# Thermocouple_Module.net
KiCad netlist of a schematic drawn in EAGLE
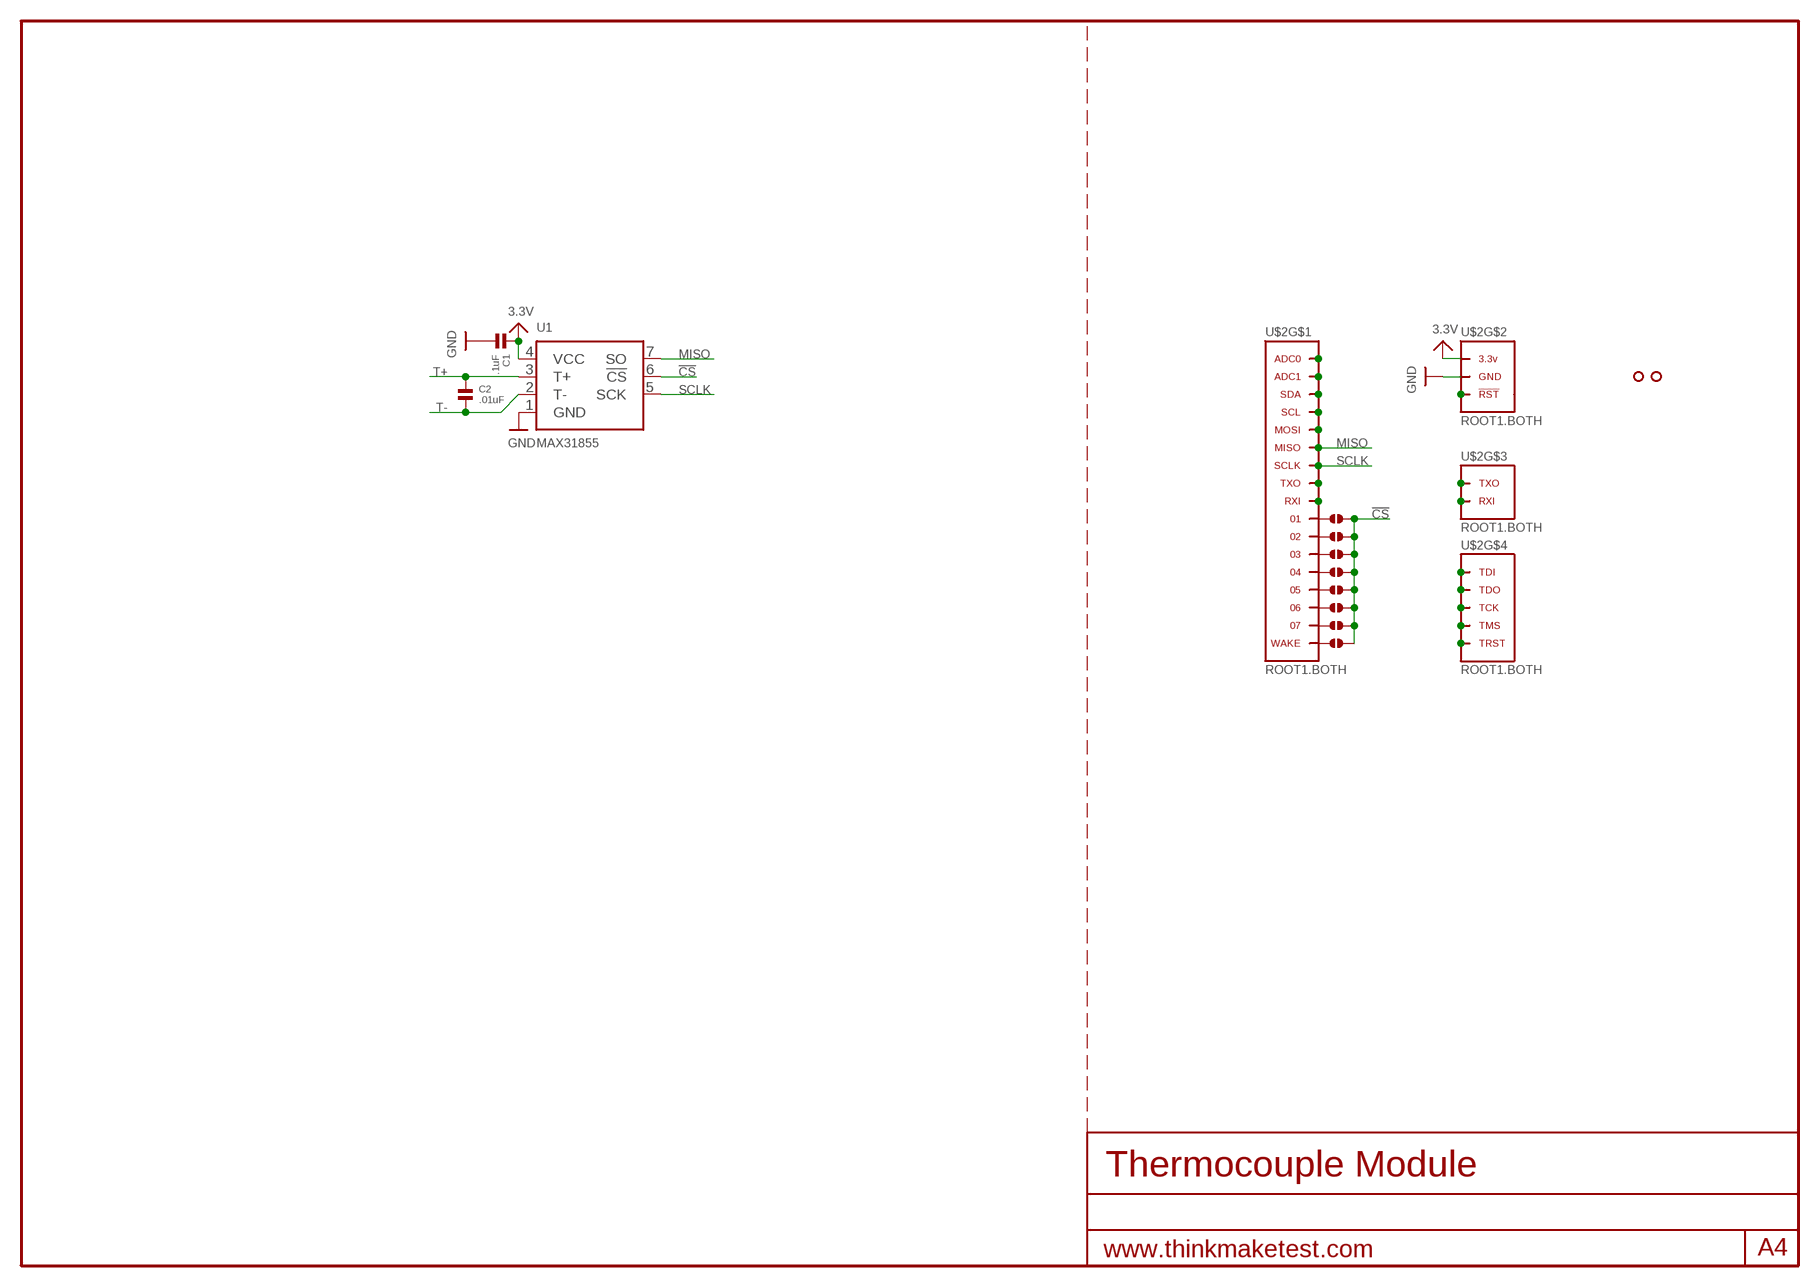
[diagram p0: schematic, sheet 1]

(export (version "E")
  (design (tool "Eeschema 10.0.6"))
  (components
    (comp (ref "C1")
      (value ".1uF")
      (footprint "eagle-import:0603")
      (libsource (lib "eagle-import") (part "CAPACITOR.0603"))
    )
    (comp (ref "C2")
      (value ".01uF")
      (footprint "eagle-import:0603")
      (libsource (lib "eagle-import") (part "CAPACITOR.0603"))
    )
    (comp (ref "J1")
      (value "SOLDERJUMPER.2.SML")
      (footprint "eagle-import:2.SML")
      (libsource (lib "eagle-import") (part "SOLDERJUMPER.2.SML"))
    )
    (comp (ref "J2")
      (value "SOLDERJUMPER.2.SML")
      (footprint "eagle-import:2.SML")
      (libsource (lib "eagle-import") (part "SOLDERJUMPER.2.SML"))
    )
    (comp (ref "J3")
      (value "SOLDERJUMPER.2.SML")
      (footprint "eagle-import:2.SML")
      (libsource (lib "eagle-import") (part "SOLDERJUMPER.2.SML"))
    )
    (comp (ref "J4")
      (value "SOLDERJUMPER.2.SML")
      (footprint "eagle-import:2.SML")
      (libsource (lib "eagle-import") (part "SOLDERJUMPER.2.SML"))
    )
    (comp (ref "J5")
      (value "SOLDERJUMPER.2.SML")
      (footprint "eagle-import:2.SML")
      (libsource (lib "eagle-import") (part "SOLDERJUMPER.2.SML"))
    )
    (comp (ref "J6")
      (value "SOLDERJUMPER.2.SML")
      (footprint "eagle-import:2.SML")
      (libsource (lib "eagle-import") (part "SOLDERJUMPER.2.SML"))
    )
    (comp (ref "J7")
      (value "SOLDERJUMPER.2.SML")
      (footprint "eagle-import:2.SML")
      (libsource (lib "eagle-import") (part "SOLDERJUMPER.2.SML"))
    )
    (comp (ref "J8")
      (value "SOLDERJUMPER.2.SML")
      (footprint "eagle-import:2.SML")
      (libsource (lib "eagle-import") (part "SOLDERJUMPER.2.SML"))
    )
    (comp (ref "U$2")
      (value "ROOT1.BOTH")
      (footprint "eagle-import:ROOT1.BOTH")
      (libsource (lib "eagle-import") (part "ROOT1.BOTH"))
    )
    (comp (ref "U$3")
      (value "HOLE.2MM")
      (footprint "eagle-import:2MM")
      (libsource (lib "eagle-import") (part "HOLE.2MM"))
    )
    (comp (ref "U$4")
      (value "HOLE.2MM")
      (footprint "eagle-import:2MM")
      (libsource (lib "eagle-import") (part "HOLE.2MM"))
    )
    (comp (ref "U1")
      (value "MAX31855")
      (footprint "eagle-import:SO08")
      (libsource (lib "eagle-import") (part "MAX31855"))
    )
  )
  (nets
    (net (code "1") (name "/MISO") (class "Default")
      (node (ref "U$2") (pin "MISO") (pinfunction "MISO_MISO") (pintype "bidirectional"))
      (node (ref "U$2") (pin "MISO@1") (pinfunction "MISO_MISO@1") (pintype "bidirectional"))
      (node (ref "U$2") (pin "MISO@VIA") (pinfunction "MISO_MISO@VIA") (pintype "bidirectional"))
      (node (ref "U1") (pin "7") (pinfunction "SO_7") (pintype "bidirectional"))
    )
    (net (code "2") (name "/SCLK") (class "Default")
      (node (ref "U$2") (pin "SCLK") (pinfunction "SCLK_SCLK") (pintype "bidirectional"))
      (node (ref "U$2") (pin "SCLK@1") (pinfunction "SCLK_SCLK@1") (pintype "bidirectional"))
      (node (ref "U$2") (pin "SCLK@VIA") (pinfunction "SCLK_SCLK@VIA") (pintype "bidirectional"))
      (node (ref "U1") (pin "5") (pinfunction "SCK_5") (pintype "bidirectional"))
    )
    (net (code "3") (name "/T+") (class "Default")
      (node (ref "C2") (pin "1") (pinfunction "1_1") (pintype "bidirectional"))
      (node (ref "U1") (pin "3") (pinfunction "T+_3") (pintype "bidirectional"))
    )
    (net (code "4") (name "/T-") (class "Default")
      (node (ref "C2") (pin "2") (pinfunction "2_2") (pintype "bidirectional"))
      (node (ref "U1") (pin "2") (pinfunction "T-_2") (pintype "bidirectional"))
    )
    (net (code "5") (name "/~{CS}") (class "Default")
      (node (ref "J1") (pin "2") (pinfunction "2_2") (pintype "bidirectional"))
      (node (ref "J2") (pin "2") (pinfunction "2_2") (pintype "bidirectional"))
      (node (ref "J3") (pin "2") (pinfunction "2_2") (pintype "bidirectional"))
      (node (ref "J4") (pin "2") (pinfunction "2_2") (pintype "bidirectional"))
      (node (ref "J5") (pin "2") (pinfunction "2_2") (pintype "bidirectional"))
      (node (ref "J6") (pin "2") (pinfunction "2_2") (pintype "bidirectional"))
      (node (ref "J7") (pin "2") (pinfunction "2_2") (pintype "bidirectional"))
      (node (ref "J8") (pin "2") (pinfunction "2_2") (pintype "bidirectional"))
      (node (ref "U1") (pin "6") (pinfunction "~{CS}_6") (pintype "bidirectional"))
    )
    (net (code "6") (name "3.3V") (class "Default")
      (node (ref "C1") (pin "1") (pinfunction "1_1") (pintype "bidirectional"))
      (node (ref "U$2") (pin "3.3V@1") (pinfunction "3.3V_3.3V@1") (pintype "bidirectional"))
      (node (ref "U$2") (pin "3.3V@10") (pinfunction "3.3V_3.3V@10") (pintype "bidirectional"))
      (node (ref "U$2") (pin "3.3V@11") (pinfunction "3.3V_3.3V@11") (pintype "bidirectional"))
      (node (ref "U$2") (pin "3.3V@12") (pinfunction "3.3V_3.3V@12") (pintype "bidirectional"))
      (node (ref "U$2") (pin "3.3V@13") (pinfunction "3.3V_3.3V@13") (pintype "bidirectional"))
      (node (ref "U$2") (pin "3.3V@14") (pinfunction "3.3V_3.3V@14") (pintype "bidirectional"))
      (node (ref "U$2") (pin "3.3V@15") (pinfunction "3.3V_3.3V@15") (pintype "bidirectional"))
      (node (ref "U$2") (pin "3.3V@16") (pinfunction "3.3V_3.3V@16") (pintype "bidirectional"))
      (node (ref "U$2") (pin "3.3V@17") (pinfunction "3.3V_3.3V@17") (pintype "bidirectional"))
      (node (ref "U$2") (pin "3.3V@18") (pinfunction "3.3V_3.3V@18") (pintype "bidirectional"))
      (node (ref "U$2") (pin "3.3V@19") (pinfunction "3.3V_3.3V@19") (pintype "bidirectional"))
      (node (ref "U$2") (pin "3.3V@2") (pinfunction "3.3V_3.3V@2") (pintype "bidirectional"))
      (node (ref "U$2") (pin "3.3V@20") (pinfunction "3.3V_3.3V@20") (pintype "bidirectional"))
      (node (ref "U$2") (pin "3.3V@21") (pinfunction "3.3V_3.3V@21") (pintype "bidirectional"))
      (node (ref "U$2") (pin "3.3V@22") (pinfunction "3.3V_3.3V@22") (pintype "bidirectional"))
      (node (ref "U$2") (pin "3.3V@23") (pinfunction "3.3V_3.3V@23") (pintype "bidirectional"))
      (node (ref "U$2") (pin "3.3V@24") (pinfunction "3.3V_3.3V@24") (pintype "bidirectional"))
      (node (ref "U$2") (pin "3.3V@3") (pinfunction "3.3V_3.3V@3") (pintype "bidirectional"))
      (node (ref "U$2") (pin "3.3V@4") (pinfunction "3.3V_3.3V@4") (pintype "bidirectional"))
      (node (ref "U$2") (pin "3.3V@5") (pinfunction "3.3V_3.3V@5") (pintype "bidirectional"))
      (node (ref "U$2") (pin "3.3V@6") (pinfunction "3.3V_3.3V@6") (pintype "bidirectional"))
      (node (ref "U$2") (pin "3.3V@7") (pinfunction "3.3V_3.3V@7") (pintype "bidirectional"))
      (node (ref "U$2") (pin "3.3V@8") (pinfunction "3.3V_3.3V@8") (pintype "bidirectional"))
      (node (ref "U$2") (pin "3.3V@9") (pinfunction "3.3V_3.3V@9") (pintype "bidirectional"))
      (node (ref "U$2") (pin "3.3V@VIA") (pinfunction "3.3V_3.3V@VIA") (pintype "bidirectional"))
      (node (ref "U1") (pin "4") (pinfunction "VCC_4") (pintype "bidirectional"))
    )
    (net (code "7") (name "GND") (class "Default")
      (node (ref "C1") (pin "2") (pinfunction "2_2") (pintype "bidirectional"))
      (node (ref "U$2") (pin "GND@1") (pinfunction "GND_GND@1") (pintype "bidirectional"))
      (node (ref "U$2") (pin "GND@10") (pinfunction "GND_GND@10") (pintype "bidirectional"))
      (node (ref "U$2") (pin "GND@11") (pinfunction "GND_GND@11") (pintype "bidirectional"))
      (node (ref "U$2") (pin "GND@12") (pinfunction "GND_GND@12") (pintype "bidirectional"))
      (node (ref "U$2") (pin "GND@13") (pinfunction "GND_GND@13") (pintype "bidirectional"))
      (node (ref "U$2") (pin "GND@14") (pinfunction "GND_GND@14") (pintype "bidirectional"))
      (node (ref "U$2") (pin "GND@15") (pinfunction "GND_GND@15") (pintype "bidirectional"))
      (node (ref "U$2") (pin "GND@16") (pinfunction "GND_GND@16") (pintype "bidirectional"))
      (node (ref "U$2") (pin "GND@17") (pinfunction "GND_GND@17") (pintype "bidirectional"))
      (node (ref "U$2") (pin "GND@18") (pinfunction "GND_GND@18") (pintype "bidirectional"))
      (node (ref "U$2") (pin "GND@19") (pinfunction "GND_GND@19") (pintype "bidirectional"))
      (node (ref "U$2") (pin "GND@2") (pinfunction "GND_GND@2") (pintype "bidirectional"))
      (node (ref "U$2") (pin "GND@20") (pinfunction "GND_GND@20") (pintype "bidirectional"))
      (node (ref "U$2") (pin "GND@21") (pinfunction "GND_GND@21") (pintype "bidirectional"))
      (node (ref "U$2") (pin "GND@22") (pinfunction "GND_GND@22") (pintype "bidirectional"))
      (node (ref "U$2") (pin "GND@23") (pinfunction "GND_GND@23") (pintype "bidirectional"))
      (node (ref "U$2") (pin "GND@24") (pinfunction "GND_GND@24") (pintype "bidirectional"))
      (node (ref "U$2") (pin "GND@25") (pinfunction "GND_GND@25") (pintype "bidirectional"))
      (node (ref "U$2") (pin "GND@26") (pinfunction "GND_GND@26") (pintype "bidirectional"))
      (node (ref "U$2") (pin "GND@3") (pinfunction "GND_GND@3") (pintype "bidirectional"))
      (node (ref "U$2") (pin "GND@4") (pinfunction "GND_GND@4") (pintype "bidirectional"))
      (node (ref "U$2") (pin "GND@5") (pinfunction "GND_GND@5") (pintype "bidirectional"))
      (node (ref "U$2") (pin "GND@6") (pinfunction "GND_GND@6") (pintype "bidirectional"))
      (node (ref "U$2") (pin "GND@7") (pinfunction "GND_GND@7") (pintype "bidirectional"))
      (node (ref "U$2") (pin "GND@8") (pinfunction "GND_GND@8") (pintype "bidirectional"))
      (node (ref "U$2") (pin "GND@9") (pinfunction "GND_GND@9") (pintype "bidirectional"))
      (node (ref "U$2") (pin "GND@VIA") (pinfunction "GND_GND@VIA") (pintype "bidirectional"))
      (node (ref "U1") (pin "1") (pinfunction "GND_1") (pintype "bidirectional"))
    )
    (net (code "8") (name "Net-(J1-Pad1)") (class "Default")
      (node (ref "J1") (pin "1") (pinfunction "1_1") (pintype "bidirectional"))
      (node (ref "U$2") (pin "01") (pinfunction "01_01") (pintype "bidirectional"))
      (node (ref "U$2") (pin "01@1") (pinfunction "01_01@1") (pintype "bidirectional"))
      (node (ref "U$2") (pin "01@VIA") (pinfunction "01_01@VIA") (pintype "bidirectional"))
    )
    (net (code "9") (name "Net-(J2-Pad1)") (class "Default")
      (node (ref "J2") (pin "1") (pinfunction "1_1") (pintype "bidirectional"))
      (node (ref "U$2") (pin "02") (pinfunction "02_02") (pintype "bidirectional"))
      (node (ref "U$2") (pin "02@1") (pinfunction "02_02@1") (pintype "bidirectional"))
      (node (ref "U$2") (pin "02@VIA") (pinfunction "02_02@VIA") (pintype "bidirectional"))
    )
    (net (code "10") (name "Net-(J3-Pad1)") (class "Default")
      (node (ref "J3") (pin "1") (pinfunction "1_1") (pintype "bidirectional"))
      (node (ref "U$2") (pin "03") (pinfunction "03_03") (pintype "bidirectional"))
      (node (ref "U$2") (pin "03@1") (pinfunction "03_03@1") (pintype "bidirectional"))
      (node (ref "U$2") (pin "03@VIA") (pinfunction "03_03@VIA") (pintype "bidirectional"))
    )
    (net (code "11") (name "Net-(J4-Pad1)") (class "Default")
      (node (ref "J4") (pin "1") (pinfunction "1_1") (pintype "bidirectional"))
      (node (ref "U$2") (pin "04") (pinfunction "04_04") (pintype "bidirectional"))
      (node (ref "U$2") (pin "04@1") (pinfunction "04_04@1") (pintype "bidirectional"))
      (node (ref "U$2") (pin "04@VIA") (pinfunction "04_04@VIA") (pintype "bidirectional"))
    )
    (net (code "12") (name "Net-(J5-Pad1)") (class "Default")
      (node (ref "J5") (pin "1") (pinfunction "1_1") (pintype "bidirectional"))
      (node (ref "U$2") (pin "05") (pinfunction "05_05") (pintype "bidirectional"))
      (node (ref "U$2") (pin "05@1") (pinfunction "05_05@1") (pintype "bidirectional"))
      (node (ref "U$2") (pin "05@VIA") (pinfunction "05_05@VIA") (pintype "bidirectional"))
    )
    (net (code "13") (name "Net-(J6-Pad1)") (class "Default")
      (node (ref "J6") (pin "1") (pinfunction "1_1") (pintype "bidirectional"))
      (node (ref "U$2") (pin "06") (pinfunction "06_06") (pintype "bidirectional"))
      (node (ref "U$2") (pin "06@1") (pinfunction "06_06@1") (pintype "bidirectional"))
      (node (ref "U$2") (pin "06@VIA") (pinfunction "06_06@VIA") (pintype "bidirectional"))
    )
    (net (code "14") (name "Net-(J7-Pad1)") (class "Default")
      (node (ref "J7") (pin "1") (pinfunction "1_1") (pintype "bidirectional"))
      (node (ref "U$2") (pin "07") (pinfunction "07_07") (pintype "bidirectional"))
      (node (ref "U$2") (pin "07@1") (pinfunction "07_07@1") (pintype "bidirectional"))
      (node (ref "U$2") (pin "07@VIA") (pinfunction "07_07@VIA") (pintype "bidirectional"))
    )
    (net (code "15") (name "Net-(J8-Pad1)") (class "Default")
      (node (ref "J8") (pin "1") (pinfunction "1_1") (pintype "bidirectional"))
      (node (ref "U$2") (pin "WAKE") (pinfunction "WAKE_WAKE") (pintype "bidirectional"))
      (node (ref "U$2") (pin "WAKE@1") (pinfunction "WAKE_WAKE@1") (pintype "bidirectional"))
      (node (ref "U$2") (pin "WAKE@VIA") (pinfunction "WAKE_WAKE@VIA") (pintype "bidirectional"))
    )
    (net (code "16") (name "Net-(U$2-PadADC0)") (class "Default")
      (node (ref "U$2") (pin "ADC0") (pinfunction "ADC0_ADC0") (pintype "bidirectional"))
      (node (ref "U$2") (pin "ADC0@1") (pinfunction "ADC0_ADC0@1") (pintype "bidirectional"))
      (node (ref "U$2") (pin "ADC0@VIA") (pinfunction "ADC0_ADC0@VIA") (pintype "bidirectional"))
    )
    (net (code "17") (name "Net-(U$2-PadADC1)") (class "Default")
      (node (ref "U$2") (pin "ADC1") (pinfunction "ADC1_ADC1") (pintype "bidirectional"))
      (node (ref "U$2") (pin "ADC1@1") (pinfunction "ADC1_ADC1@1") (pintype "bidirectional"))
      (node (ref "U$2") (pin "ADC1@VIA") (pinfunction "ADC1_ADC1@VIA") (pintype "bidirectional"))
    )
    (net (code "18") (name "Net-(U$2-PadMOSI)") (class "Default")
      (node (ref "U$2") (pin "MOSI") (pinfunction "MOSI_MOSI") (pintype "bidirectional"))
      (node (ref "U$2") (pin "MOSI@1") (pinfunction "MOSI_MOSI@1") (pintype "bidirectional"))
      (node (ref "U$2") (pin "MOSI@VIA") (pinfunction "MOSI_MOSI@VIA") (pintype "bidirectional"))
    )
    (net (code "19") (name "Net-(U$2-PadRXI)") (class "Default")
      (node (ref "U$2") (pin "RXI") (pinfunction "RXI_RXI") (pintype "bidirectional"))
      (node (ref "U$2") (pin "RXI@1") (pinfunction "RXI_RXI@1") (pintype "bidirectional"))
      (node (ref "U$2") (pin "RXI@VIA") (pinfunction "RXI_RXI@VIA") (pintype "bidirectional"))
    )
    (net (code "20") (name "Net-(U$2-PadSCL)") (class "Default")
      (node (ref "U$2") (pin "SCL") (pinfunction "SCL_SCL") (pintype "bidirectional"))
      (node (ref "U$2") (pin "SCL@1") (pinfunction "SCL_SCL@1") (pintype "bidirectional"))
      (node (ref "U$2") (pin "SCL@VIA") (pinfunction "SCL_SCL@VIA") (pintype "bidirectional"))
    )
    (net (code "21") (name "Net-(U$2-PadSDA)") (class "Default")
      (node (ref "U$2") (pin "SDA") (pinfunction "SDA_SDA") (pintype "bidirectional"))
      (node (ref "U$2") (pin "SDA@1") (pinfunction "SDA_SDA@1") (pintype "bidirectional"))
      (node (ref "U$2") (pin "SDA@VIA") (pinfunction "SDA_SDA@VIA") (pintype "bidirectional"))
    )
    (net (code "22") (name "Net-(U$2-PadTCK)") (class "Default")
      (node (ref "U$2") (pin "TCK") (pinfunction "TCK_TCK") (pintype "bidirectional"))
      (node (ref "U$2") (pin "TCK@1") (pinfunction "TCK_TCK@1") (pintype "bidirectional"))
      (node (ref "U$2") (pin "TCK@VIA") (pinfunction "TCK_TCK@VIA") (pintype "bidirectional"))
    )
    (net (code "23") (name "Net-(U$2-PadTDI)") (class "Default")
      (node (ref "U$2") (pin "TDI") (pinfunction "TDI_TDI") (pintype "bidirectional"))
      (node (ref "U$2") (pin "TDI@1") (pinfunction "TDI_TDI@1") (pintype "bidirectional"))
      (node (ref "U$2") (pin "TDI@VIA") (pinfunction "TDI_TDI@VIA") (pintype "bidirectional"))
    )
    (net (code "24") (name "Net-(U$2-PadTDO)") (class "Default")
      (node (ref "U$2") (pin "TDO") (pinfunction "TDO_TDO") (pintype "bidirectional"))
      (node (ref "U$2") (pin "TDO@1") (pinfunction "TDO_TDO@1") (pintype "bidirectional"))
      (node (ref "U$2") (pin "TDO@VIA") (pinfunction "TDO_TDO@VIA") (pintype "bidirectional"))
    )
    (net (code "25") (name "Net-(U$2-PadTMS)") (class "Default")
      (node (ref "U$2") (pin "TMS") (pinfunction "TMS_TMS") (pintype "bidirectional"))
      (node (ref "U$2") (pin "TMS@1") (pinfunction "TMS_TMS@1") (pintype "bidirectional"))
      (node (ref "U$2") (pin "TMS@VIA") (pinfunction "TMS_TMS@VIA") (pintype "bidirectional"))
    )
    (net (code "26") (name "Net-(U$2-PadTRST)") (class "Default")
      (node (ref "U$2") (pin "TRST") (pinfunction "TRST_TRST") (pintype "bidirectional"))
      (node (ref "U$2") (pin "TRST@1") (pinfunction "TRST_TRST@1") (pintype "bidirectional"))
      (node (ref "U$2") (pin "TRST@VIA") (pinfunction "TRST_TRST@VIA") (pintype "bidirectional"))
    )
    (net (code "27") (name "Net-(U$2-PadTXO)") (class "Default")
      (node (ref "U$2") (pin "TXO") (pinfunction "TXO_TXO") (pintype "bidirectional"))
      (node (ref "U$2") (pin "TXO@1") (pinfunction "TXO_TXO@1") (pintype "bidirectional"))
      (node (ref "U$2") (pin "TXO@VIA") (pinfunction "TXO_TXO@VIA") (pintype "bidirectional"))
    )
    (net (code "28") (name "Net-(U$2B-~{RST}-PadRST)") (class "Default")
      (node (ref "U$2") (pin "RST") (pinfunction "~{RST}_RST") (pintype "bidirectional"))
      (node (ref "U$2") (pin "RST@1") (pinfunction "~{RST}_RST@1") (pintype "bidirectional"))
      (node (ref "U$2") (pin "RST@VIA") (pinfunction "~{RST}_RST@VIA") (pintype "bidirectional"))
    )
    (net (code "29") (name "Net-(U$2C-RXI-PadRXI.DBG)") (class "Default")
      (node (ref "U$2") (pin "RXI.DBG") (pinfunction "RXI_RXI.DBG") (pintype "bidirectional"))
      (node (ref "U$2") (pin "RXI.DBG@1") (pinfunction "RXI_RXI.DBG@1") (pintype "bidirectional"))
      (node (ref "U$2") (pin "RXI.DBG@VIA") (pinfunction "RXI_RXI.DBG@VIA") (pintype "bidirectional"))
    )
    (net (code "30") (name "Net-(U$2C-TXO-PadTXO.DBG)") (class "Default")
      (node (ref "U$2") (pin "TXO.DBG") (pinfunction "TXO_TXO.DBG") (pintype "bidirectional"))
      (node (ref "U$2") (pin "TXO.DBG@1") (pinfunction "TXO_TXO.DBG@1") (pintype "bidirectional"))
      (node (ref "U$2") (pin "TXO.DBG@VIA") (pinfunction "TXO_TXO.DBG@VIA") (pintype "bidirectional"))
    )
  )
)
